# DT_JFET_Pre.net
KiCad netlist of a schematic drawn in Altium Designer
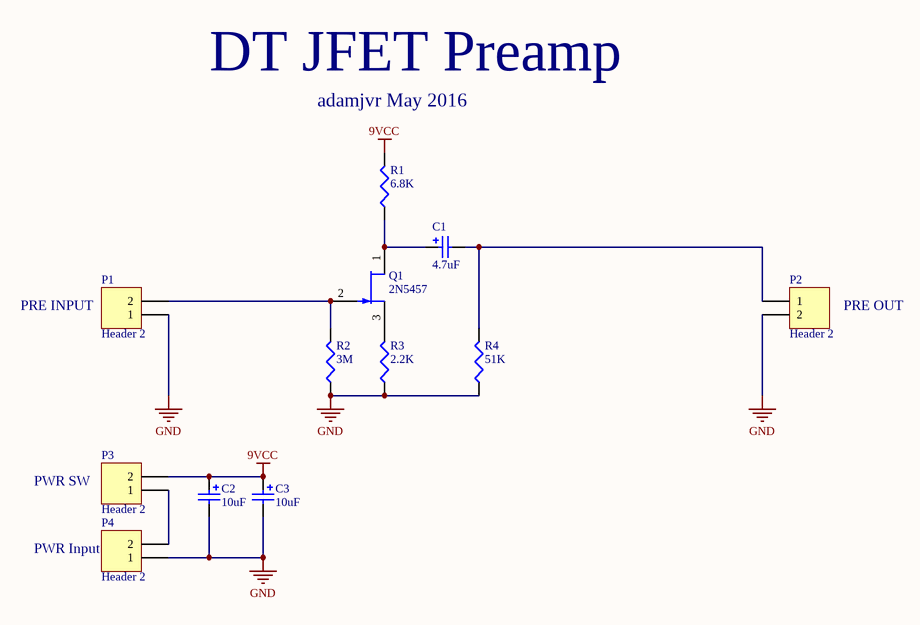
[diagram p0: DT JFET Pre.SchDoc]

(export (version "E")
  (design (tool "Eeschema 10.0.6"))
  (components
    (comp (ref "C1")
      (value "4.7uF")
      (footprint "4X6mmCAP")
      (description "CAP ALUM 4.7UF 20% 35V RADIAL")
      (fields
        (field (name "MFR") "Nichicon")
        (field (name "TOLERANCE") "20%")
        (field (name "DESIGNER") "Adam Vadala-Roth")
      )
      (libsource (lib "AudioPartLib") (part "UMW1V4R7MDD1TP"))
    )
    (comp (ref "C2")
      (value "10uF")
      (footprint "4X6mmCAP")
      (description "CAP ALUM 10UF 20% 16V RADIAL")
      (fields
        (field (name "MFR") "Nichicon")
        (field (name "TOLERANCE") "20%")
        (field (name "DESIGNER") "Adam Vadala-Roth")
      )
      (libsource (lib "AudioPartLib") (part "UMW1C100MDD1TP"))
    )
    (comp (ref "C3")
      (value "10uF")
      (footprint "4X6mmCAP")
      (description "CAP ALUM 10UF 20% 16V RADIAL")
      (fields
        (field (name "MFR") "Nichicon")
        (field (name "TOLERANCE") "20%")
        (field (name "DESIGNER") "Adam Vadala-Roth")
      )
      (libsource (lib "AudioPartLib") (part "UMW1C100MDD1TP"))
    )
    (comp (ref "P1")
      (value "Header 2")
      (footprint "HDR1X2")
      (description "Header, 2-Pin")
      (fields (field (name "PUBLISHER") "Altium Limited"))
      (libsource (lib "Miscellaneous Connectors") (part "Header 2"))
    )
    (comp (ref "P2")
      (value "Header 2")
      (footprint "HDR1X2")
      (description "Header, 2-Pin")
      (fields (field (name "PUBLISHER") "Altium Limited"))
      (libsource (lib "") (part "Header 2_1"))
    )
    (comp (ref "P3")
      (value "Header 2")
      (footprint "HDR1X2")
      (description "Header, 2-Pin")
      (fields (field (name "PUBLISHER") "Altium Limited"))
      (libsource (lib "Miscellaneous Connectors") (part "Header 2"))
    )
    (comp (ref "P4")
      (value "Header 2")
      (footprint "HDR1X2")
      (description "Header, 2-Pin")
      (fields (field (name "PUBLISHER") "Altium Limited"))
      (libsource (lib "Miscellaneous Connectors") (part "Header 2"))
    )
    (comp (ref "Q1")
      (value "2N5457")
      (footprint "TO-92A")
      (description "JFET N-CH 25V 0.31W TO-92")
      (fields
        (field (name "MFR") "Central-Semiconductor-Corp")
        (field (name "VOLTAGE") "25V")
        (field (name "DESIGNER") "Adam Vadala-Roth")
      )
      (libsource (lib "AudioPartLib") (part "2N5457"))
    )
    (comp (ref "R1")
      (value "6.8K")
      (footprint "R0805")
      (description "RES SMD 6.8K OHM 1% 1/8W 0805")
      (fields
        (field (name "MFR") "Samsung-Electro-Mechanics-America,-Inc.")
        (field (name "TOLERANCE") "1%")
        (field (name "DESIGNER") "Adam Vadala-Roth")
      )
      (libsource (lib "AudioPartLib") (part "RC2012F682CS"))
    )
    (comp (ref "R2")
      (value "3M")
      (footprint "R0805")
      (description "RES SMD 3M OHM 1% 1/8W 0805")
      (fields
        (field (name "MFR") "Samsung-Electro-Mechanics-America,-Inc.")
        (field (name "TOLERANCE") "1%")
        (field (name "DESIGNER") "Adam Vadala-Roth")
      )
      (libsource (lib "AudioPartLib") (part "RC2012F305CS"))
    )
    (comp (ref "R3")
      (value "2.2K")
      (footprint "R0805")
      (description "RES SMD 2.2K OHM 1% 1/8W 0805")
      (fields
        (field (name "MFR") "Samsung-Electro-Mechanics-America,-Inc.")
        (field (name "TOLERANCE") "1%")
        (field (name "DESIGNER") "Adam Vadala-Roth")
      )
      (libsource (lib "AudioPartLib") (part "RC2012F222CS"))
    )
    (comp (ref "R4")
      (value "51K")
      (footprint "R0805")
      (description "RES SMD 51K OHM 1% 1/8W 0805")
      (fields
        (field (name "MFR") "Samsung-Electro-Mechanics-America,-Inc.")
        (field (name "TOLERANCE") "1%")
        (field (name "DESIGNER") "Adam Vadala-Roth")
      )
      (libsource (lib "AudioPartLib") (part "RC2012F513CS"))
    )
  )
  (nets
    (net (code "1") (name "9VCC") (class "Default")
      (node (ref "C2") (pin "1") (pinfunction "1_1") (pintype "passive"))
      (node (ref "C3") (pin "1") (pinfunction "1_1") (pintype "passive"))
      (node (ref "P3") (pin "2") (pinfunction "2_2") (pintype "passive"))
      (node (ref "R1") (pin "2") (pinfunction "2_2") (pintype "passive"))
    )
    (net (code "2") (name "GND") (class "Default")
      (node (ref "C2") (pin "2") (pinfunction "2_2") (pintype "passive"))
      (node (ref "C3") (pin "2") (pinfunction "2_2") (pintype "passive"))
      (node (ref "P1") (pin "1") (pinfunction "1_1") (pintype "passive"))
      (node (ref "P2") (pin "2") (pinfunction "2_2") (pintype "passive"))
      (node (ref "P4") (pin "1") (pinfunction "1_1") (pintype "passive"))
      (node (ref "R2") (pin "1") (pinfunction "1_1") (pintype "passive"))
      (node (ref "R3") (pin "1") (pinfunction "1_1") (pintype "passive"))
      (node (ref "R4") (pin "1") (pinfunction "1_1") (pintype "passive"))
    )
    (net (code "3") (name "Net-(C1-Pad2)") (class "Default")
      (node (ref "C1") (pin "2") (pinfunction "2_2") (pintype "passive"))
      (node (ref "P2") (pin "1") (pinfunction "1_1") (pintype "passive"))
      (node (ref "R4") (pin "2") (pinfunction "2_2") (pintype "passive"))
    )
    (net (code "4") (name "Net-(P3-Pad1)") (class "Default")
      (node (ref "P3") (pin "1") (pinfunction "1_1") (pintype "passive"))
      (node (ref "P4") (pin "2") (pinfunction "2_2") (pintype "passive"))
    )
    (net (code "5") (name "Net-(Q1-D)") (class "Default")
      (node (ref "C1") (pin "1") (pinfunction "1_1") (pintype "passive"))
      (node (ref "Q1") (pin "1") (pinfunction "D_1") (pintype "passive"))
      (node (ref "R1") (pin "1") (pinfunction "1_1") (pintype "passive"))
    )
    (net (code "6") (name "Net-(Q1-G)") (class "Default")
      (node (ref "P1") (pin "2") (pinfunction "2_2") (pintype "passive"))
      (node (ref "Q1") (pin "2") (pinfunction "G_2") (pintype "passive"))
      (node (ref "R2") (pin "2") (pinfunction "2_2") (pintype "passive"))
    )
    (net (code "7") (name "Net-(Q1-S)") (class "Default")
      (node (ref "Q1") (pin "3") (pinfunction "S_3") (pintype "passive"))
      (node (ref "R3") (pin "2") (pinfunction "2_2") (pintype "passive"))
    )
  )
)
